# debug.net
KiCad netlist of a schematic drawn in Altium Designer
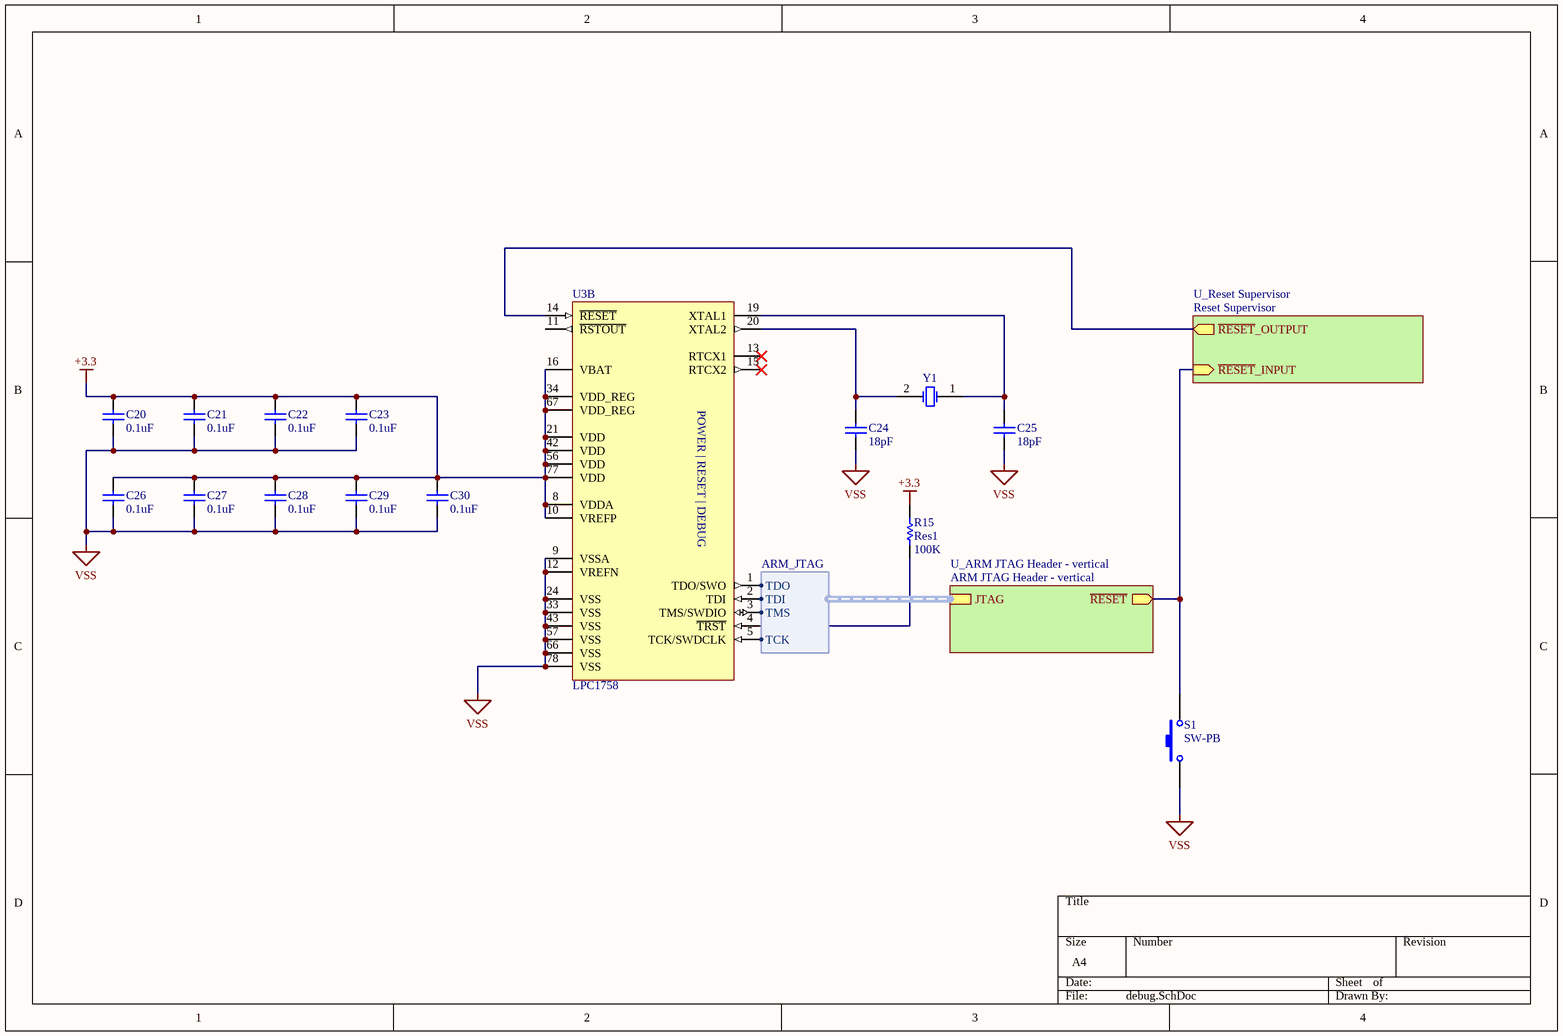
[diagram p0: debug.SchDoc]

(export (version "E")
  (design (tool "Eeschema 10.0.6"))
  (components
    (comp (ref "C20")
      (value "0.1uF")
      (footprint "C0805")
      (description "Capacitor")
      (fields (field (name "Comment") "Cap") (field (name "PUBLISHER") "Altium Limited"))
      (libsource (lib "Miscellaneous Devices") (part "Cap"))
    )
    (comp (ref "C21")
      (value "0.1uF")
      (footprint "C0805")
      (description "Capacitor")
      (fields (field (name "Comment") "Cap") (field (name "PUBLISHER") "Altium Limited"))
      (libsource (lib "Miscellaneous Devices") (part "Cap"))
    )
    (comp (ref "C22")
      (value "0.1uF")
      (footprint "C0805")
      (description "Capacitor")
      (fields (field (name "Comment") "Cap") (field (name "PUBLISHER") "Altium Limited"))
      (libsource (lib "Miscellaneous Devices") (part "Cap"))
    )
    (comp (ref "C23")
      (value "0.1uF")
      (footprint "C0805")
      (description "Capacitor")
      (fields (field (name "Comment") "Cap") (field (name "PUBLISHER") "Altium Limited"))
      (libsource (lib "Miscellaneous Devices") (part "Cap"))
    )
    (comp (ref "C24")
      (value "18pF")
      (footprint "C0805")
      (description "Capacitor")
      (fields (field (name "Comment") "Cap") (field (name "PUBLISHER") "Altium Limited"))
      (libsource (lib "Miscellaneous Devices") (part "Cap"))
    )
    (comp (ref "C25")
      (value "18pF")
      (footprint "C0805")
      (description "Capacitor")
      (fields (field (name "Comment") "Cap") (field (name "PUBLISHER") "Altium Limited"))
      (libsource (lib "Miscellaneous Devices") (part "Cap"))
    )
    (comp (ref "C26")
      (value "0.1uF")
      (footprint "C0805")
      (description "Capacitor")
      (fields (field (name "Comment") "Cap") (field (name "PUBLISHER") "Altium Limited"))
      (libsource (lib "Miscellaneous Devices") (part "Cap"))
    )
    (comp (ref "C27")
      (value "0.1uF")
      (footprint "C0805")
      (description "Capacitor")
      (fields (field (name "Comment") "Cap") (field (name "PUBLISHER") "Altium Limited"))
      (libsource (lib "Miscellaneous Devices") (part "Cap"))
    )
    (comp (ref "C28")
      (value "0.1uF")
      (footprint "C0805")
      (description "Capacitor")
      (fields (field (name "Comment") "Cap") (field (name "PUBLISHER") "Altium Limited"))
      (libsource (lib "Miscellaneous Devices") (part "Cap"))
    )
    (comp (ref "C29")
      (value "0.1uF")
      (footprint "C0805")
      (description "Capacitor")
      (fields (field (name "Comment") "Cap") (field (name "PUBLISHER") "Altium Limited"))
      (libsource (lib "Miscellaneous Devices") (part "Cap"))
    )
    (comp (ref "C30")
      (value "0.1uF")
      (footprint "C0805")
      (description "Capacitor")
      (fields (field (name "Comment") "Cap") (field (name "PUBLISHER") "Altium Limited"))
      (libsource (lib "Miscellaneous Devices") (part "Cap"))
    )
    (comp (ref "R15")
      (value "Res1")
      (footprint "R0603")
      (description "Resistor")
      (fields (field (name "ALTIUM_VALUE") "100K") (field (name "PUBLISHER") "Altium Limited"))
      (libsource (lib "Miscellaneous Devices") (part "Res1"))
    )
    (comp (ref "S1")
      (value "SW-PB")
      (footprint "DTSM-32S-B")
      (description "Switch")
      (fields (field (name "PUBLISHER") "Altium Limited"))
      (libsource (lib "Miscellaneous Devices") (part "SW-PB"))
    )
    (comp (ref "U3")
      (value "LPC1758")
      (footprint "LPC1758FBD80")
      (description "NXP - LPC1758FBD80 - MCU, 32BIT, ARM CORTEX M3, 80LQFP")
      (libsource (lib "LPC1758") (part "LPC1758"))
    )
    (comp (ref "Y1")
      (value "XTAL")
      (footprint "C3E-24.000-12-3030-X")
      (description "Crystal Oscillator")
      (fields (field (name "PUBLISHER") "Altium Limited"))
      (libsource (lib "Miscellaneous Devices") (part "XTAL"))
    )
  )
  (nets
    (net (code "2") (name "+3.3") (class "Default")
      (node (ref "C20") (pin "1") (pinfunction "1_1") (pintype "passive"))
      (node (ref "C21") (pin "1") (pinfunction "1_1") (pintype "passive"))
      (node (ref "C22") (pin "1") (pinfunction "1_1") (pintype "passive"))
      (node (ref "C23") (pin "1") (pinfunction "1_1") (pintype "passive"))
      (node (ref "C26") (pin "1") (pinfunction "1_1") (pintype "passive"))
      (node (ref "C27") (pin "1") (pinfunction "1_1") (pintype "passive"))
      (node (ref "C28") (pin "1") (pinfunction "1_1") (pintype "passive"))
      (node (ref "C29") (pin "1") (pinfunction "1_1") (pintype "passive"))
      (node (ref "C30") (pin "1") (pinfunction "1_1") (pintype "passive"))
      (node (ref "R15") (pin "2") (pinfunction "2_2") (pintype "passive"))
      (node (ref "U3") (pin "10") (pinfunction "VREFP_10") (pintype "passive"))
      (node (ref "U3") (pin "16") (pinfunction "VBAT_16") (pintype "power_in"))
      (node (ref "U3") (pin "21") (pinfunction "VDD_21") (pintype "power_in"))
      (node (ref "U3") (pin "34") (pinfunction "VDD_REG_34") (pintype "power_in"))
      (node (ref "U3") (pin "42") (pinfunction "VDD_42") (pintype "power_in"))
      (node (ref "U3") (pin "56") (pinfunction "VDD_56") (pintype "power_in"))
      (node (ref "U3") (pin "67") (pinfunction "VDD_REG_67") (pintype "power_in"))
      (node (ref "U3") (pin "77") (pinfunction "VDD_77") (pintype "power_in"))
      (node (ref "U3") (pin "8") (pinfunction "VDDA_8") (pintype "power_in"))
    )
    (net (code "3") (name "/TCK") (class "Default")
      (node (ref "U3") (pin "5") (pinfunction "TCK/SWDCLK_5") (pintype "input"))
    )
    (net (code "4") (name "/TDI") (class "Default")
      (node (ref "U3") (pin "2") (pinfunction "TDI_2") (pintype "input"))
    )
    (net (code "5") (name "/TDO") (class "Default")
      (node (ref "U3") (pin "1") (pinfunction "TDO/SWO_1") (pintype "output"))
    )
    (net (code "6") (name "/TMS") (class "Default")
      (node (ref "U3") (pin "3") (pinfunction "TMS/SWDIO_3") (pintype "bidirectional"))
    )
    (net (code "8") (name "/~{RESET}") (class "Default")
      (node (ref "S1") (pin "2") (pinfunction "2_2") (pintype "passive"))
    )
    (net (code "9") (name "/~{RESET}_OUTPUT") (class "Default")
      (node (ref "U3") (pin "14") (pinfunction "~{RESET}_14") (pintype "input"))
    )
    (net (code "10") (name "Net-(U3B-XTAL1)") (class "Default")
      (node (ref "C25") (pin "1") (pinfunction "1_1") (pintype "passive"))
      (node (ref "U3") (pin "19") (pinfunction "XTAL1_19") (pintype "passive"))
      (node (ref "Y1") (pin "1") (pinfunction "OSC1_1") (pintype "passive"))
    )
    (net (code "11") (name "Net-(U3B-XTAL2)") (class "Default")
      (node (ref "C24") (pin "1") (pinfunction "1_1") (pintype "passive"))
      (node (ref "U3") (pin "20") (pinfunction "XTAL2_20") (pintype "output"))
      (node (ref "Y1") (pin "2") (pinfunction "OSC2_2") (pintype "passive"))
    )
    (net (code "12") (name "Net-(U3B-~{TRST})") (class "Default")
      (node (ref "R15") (pin "1") (pinfunction "1_1") (pintype "passive"))
      (node (ref "U3") (pin "4") (pinfunction "~{TRST}_4") (pintype "input"))
    )
    (net (code "13") (name "VSS") (class "Default")
      (node (ref "C20") (pin "2") (pinfunction "2_2") (pintype "passive"))
      (node (ref "C21") (pin "2") (pinfunction "2_2") (pintype "passive"))
      (node (ref "C22") (pin "2") (pinfunction "2_2") (pintype "passive"))
      (node (ref "C23") (pin "2") (pinfunction "2_2") (pintype "passive"))
      (node (ref "C24") (pin "2") (pinfunction "2_2") (pintype "passive"))
      (node (ref "C25") (pin "2") (pinfunction "2_2") (pintype "passive"))
      (node (ref "C26") (pin "2") (pinfunction "2_2") (pintype "passive"))
      (node (ref "C27") (pin "2") (pinfunction "2_2") (pintype "passive"))
      (node (ref "C28") (pin "2") (pinfunction "2_2") (pintype "passive"))
      (node (ref "C29") (pin "2") (pinfunction "2_2") (pintype "passive"))
      (node (ref "C30") (pin "2") (pinfunction "2_2") (pintype "passive"))
      (node (ref "S1") (pin "1") (pinfunction "1_1") (pintype "passive"))
      (node (ref "U3") (pin "12") (pinfunction "VREFN_12") (pintype "passive"))
      (node (ref "U3") (pin "24") (pinfunction "VSS_24") (pintype "power_in"))
      (node (ref "U3") (pin "33") (pinfunction "VSS_33") (pintype "power_in"))
      (node (ref "U3") (pin "43") (pinfunction "VSS_43") (pintype "power_in"))
      (node (ref "U3") (pin "57") (pinfunction "VSS_57") (pintype "power_in"))
      (node (ref "U3") (pin "66") (pinfunction "VSS_66") (pintype "power_in"))
      (node (ref "U3") (pin "78") (pinfunction "VSS_78") (pintype "power_in"))
      (node (ref "U3") (pin "9") (pinfunction "VSSA_9") (pintype "power_in"))
    )
    (net (code "14") (name "unconnected-(U3B-RTCX1-Pad13)") (class "Default")
      (node (ref "U3") (pin "13") (pinfunction "RTCX1_13") (pintype "passive+no_connect"))
    )
    (net (code "15") (name "unconnected-(U3B-RTCX2-Pad15)") (class "Default")
      (node (ref "U3") (pin "15") (pinfunction "RTCX2_15") (pintype "output+no_connect"))
    )
    (net (code "16") (name "unconnected-(U3B-~{RSTOUT}-Pad11)") (class "Default")
      (node (ref "U3") (pin "11") (pinfunction "~{RSTOUT}_11") (pintype "output"))
    )
  )
)
